# BQ51003YFPT_WirelessCharger_2_5W.net
KiCad netlist of a schematic drawn in Altium Designer
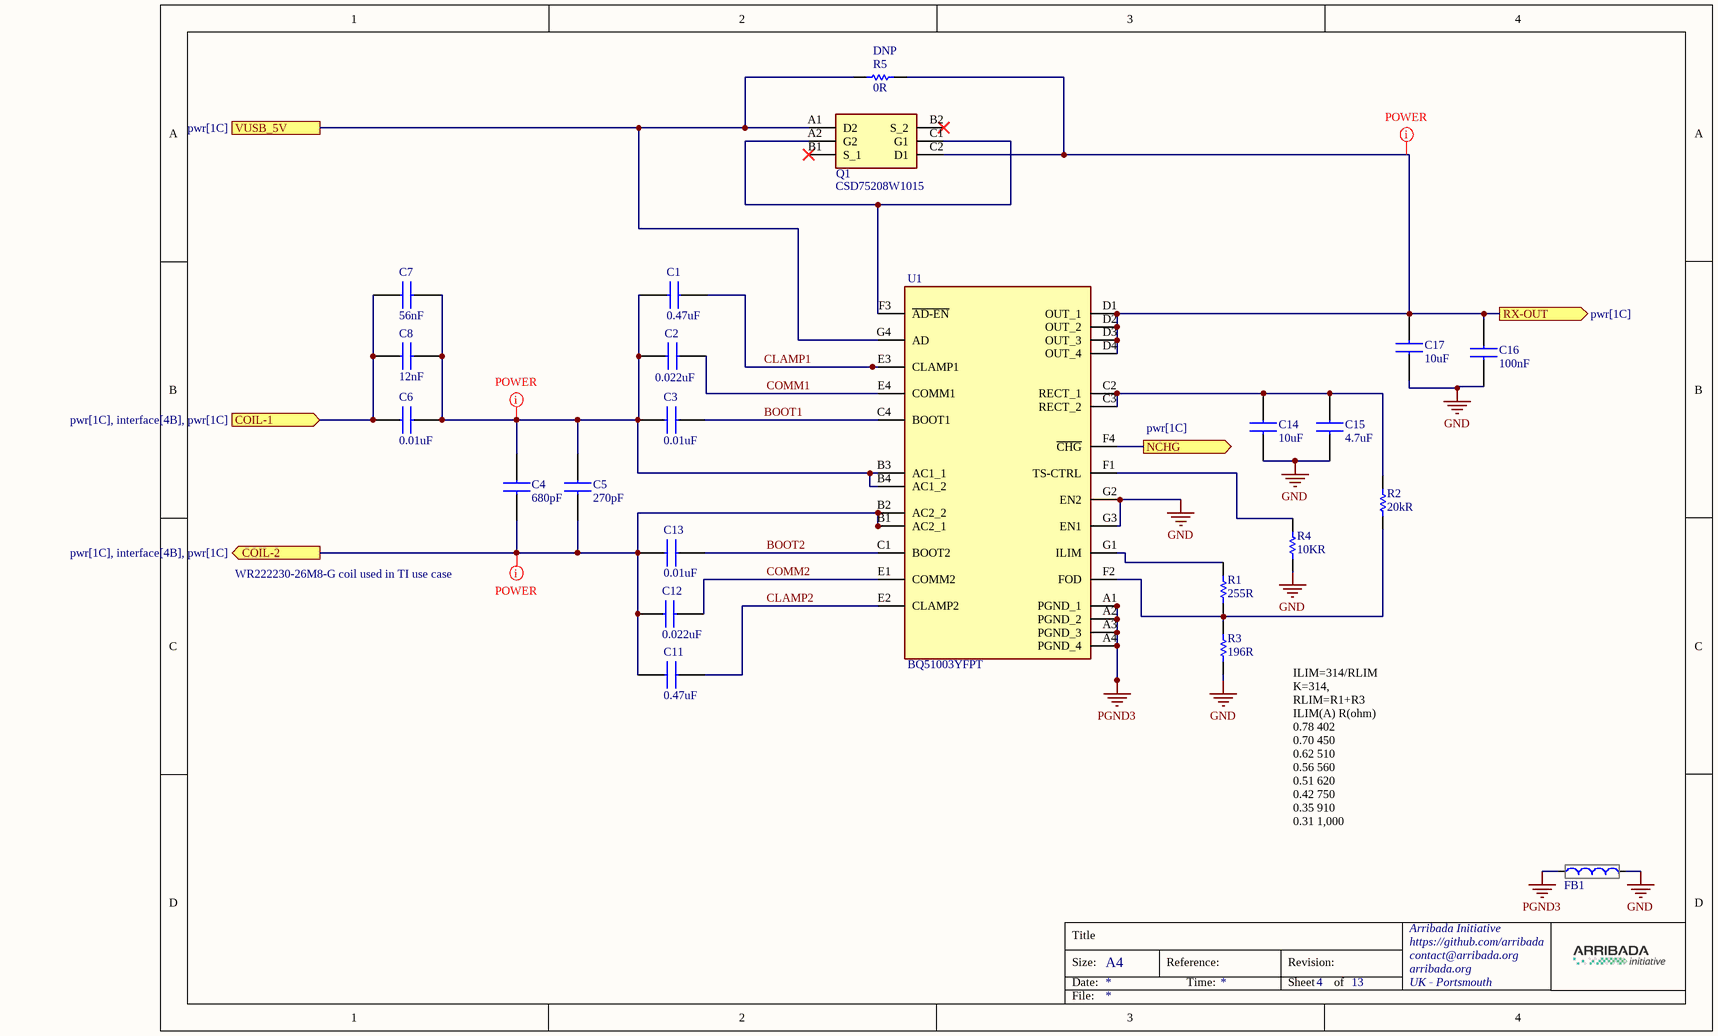
[diagram p0: BQ51003YFPT_WirelessCharger_2.5W.SchDoc]

(export (version "E")
  (design (tool "Eeschema 10.0.6"))
  (components
    (comp (ref "C1")
      (value "0.47uF")
      (footprint "stm32wl-dev:GRM18x")
      (description "Multilayer Ceramic Capacitors MLCC - SMD/SMT 0.47 uF 25 VDC 10% 0603 X7R")
      (fields
        (field (name "MANUFACTURER_PART_NUMBER") "GRM188R71E474KA12D")
        (field (name "MOUSER PART NUMBER") "81-GRM188R71E474KA12")
      )
      (libsource (lib "stm32wl-dev") (part "GRM188R71E474KA12D"))
    )
    (comp (ref "C2")
      (value "0.022uF")
      (footprint "stm32wl-dev:GRM15x")
      (description "Multilayer Ceramic Capacitors MLCC - SMD/SMT 0.022 uF 25 VDC 10% 0402 X7R")
      (fields
        (field (name "MANUFACTURER_PART_NUMBER") "GRM155R71E223KA61D")
        (field (name "MOUSER PART NUMBER") "81-GRM155R71E223KA6D")
      )
      (libsource (lib "stm32wl-dev") (part "GRM155R71E223KA61D"))
    )
    (comp (ref "C3")
      (value "0.01uF")
      (footprint "stm32wl-dev:CAPC1005X70N")
      (description "Multilayer Ceramic Capacitors MLCC - SMD/SMT 0.01 uF 25 VDC 10% 0402 X7R")
      (fields
        (field (name "MANUFACTURER_PART_NUMBER") "GRM155R71E103KA01D")
        (field (name "MOUSER PART NUMBER") "81-GRM36X103K25")
      )
      (libsource (lib "stm32wl-dev") (part "GRM155R71E103KA01D"))
    )
    (comp (ref "C4")
      (value "680pF")
      (footprint "stm32wl-dev:CAPC1005X70N")
      (description "Multilayer Ceramic Capacitors MLCC - SMD/SMT 680 pF 50 VDC 10% 0402 X7R")
      (fields
        (field (name "MANUFACTURER_PART_NUMBER") "GRM155R71H681KA01D")
        (field (name "MOUSER PART NUMBER") "81-GRM15R71H681KA01D")
      )
      (libsource (lib "stm32wl-dev") (part "GRM155R71H681KA01D"))
    )
    (comp (ref "C5")
      (value "270pF")
      (footprint "stm32wl-dev:CAPC1005X70N")
      (description "Multilayer Ceramic Capacitors MLCC - SMD/SMT 270 pF 50 VDC 10% 0402 X7R")
      (fields
        (field (name "MANUFACTURER_PART_NUMBER") "GRM155R71H271KA01J")
        (field (name "MOUSER PART NUMBER") "81-GRM155R71H271KA1J")
      )
      (libsource (lib "stm32wl-dev") (part "GRM155R71H271KA01J"))
    )
    (comp (ref "C6")
      (value "0.01uF")
      (footprint "stm32wl-dev:CAPC1608X90N")
      (description "Multilayer Ceramic Capacitors MLCC - SMD/SMT .01UF 50V 10% 0603")
      (fields
        (field (name "MANUFACTURER_PART_NUMBER") "GRM188R71H103KA01D")
        (field (name "MOUSER PART NUMBER") "81-GRM39X103K50D")
      )
      (libsource (lib "stm32wl-dev") (part "GRM188R71H103KA01D"))
    )
    (comp (ref "C7")
      (value "56nF")
      (footprint "stm32wl-dev:CAPC1608X90N")
      (description "Multilayer Ceramic Capacitors MLCC - SMD/SMT 0.056 uF 50 VDC 10% 0603 X7R AEC-Q200")
      (fields (field (name "MANUFACTURER_PART_NUMBER") "GCJ188R71H563KA12J"))
      (libsource (lib "stm32wl-dev") (part "GCJ188R71H563KA12J"))
    )
    (comp (ref "C8")
      (value "12nF")
      (footprint "CAPC1608X90N")
      (description "Multilayer Ceramic Capacitors MLCC - SMD/SMT 50V 0.012uF X7R 0603 10%")
      (fields
        (field (name "MANUFACTURER") "KEMET")
        (field (name "MANUFACTURER PART NUMBER") "C0603C123K5RACTU")
      )
      (libsource (lib "stm32wl-dev") (part "C0603C123K5RACTU"))
    )
    (comp (ref "C11")
      (value "0.47uF")
      (footprint "stm32wl-dev:GRM18x")
      (description "Multilayer Ceramic Capacitors MLCC - SMD/SMT 0.47 uF 25 VDC 10% 0603 X7R")
      (fields
        (field (name "MANUFACTURER_PART_NUMBER") "GRM188R71E474KA12D")
        (field (name "MOUSER PART NUMBER") "81-GRM188R71E474KA12")
      )
      (libsource (lib "stm32wl-dev") (part "GRM188R71E474KA12D"))
    )
    (comp (ref "C12")
      (value "0.022uF")
      (footprint "stm32wl-dev:GRM15x")
      (description "Multilayer Ceramic Capacitors MLCC - SMD/SMT 0.022 uF 25 VDC 10% 0402 X7R")
      (fields
        (field (name "MANUFACTURER_PART_NUMBER") "GRM155R71E223KA61D")
        (field (name "MOUSER PART NUMBER") "81-GRM155R71E223KA6D")
      )
      (libsource (lib "stm32wl-dev") (part "GRM155R71E223KA61D"))
    )
    (comp (ref "C13")
      (value "0.01uF")
      (footprint "stm32wl-dev:CAPC1005X70N")
      (description "Multilayer Ceramic Capacitors MLCC - SMD/SMT 0.01 uF 25 VDC 10% 0402 X7R")
      (fields
        (field (name "MANUFACTURER_PART_NUMBER") "GRM155R71E103KA01D")
        (field (name "MOUSER PART NUMBER") "81-GRM36X103K25")
      )
      (libsource (lib "stm32wl-dev") (part "GRM155R71E103KA01D"))
    )
    (comp (ref "C14")
      (value "EMK107BBJ106MA-T")
      (footprint "stm32wl-dev:CAPC1709X100N")
      (description "Multilayer Ceramic Capacitors MLCC - SMD/SMT 963-MSASE168BB5106MT RPLCMT PN 16V 10uF X5R 0603 20%")
      (fields (field (name "MOUSER PART NUMBER") "963-EMK107BBJ106MA-T") (field (name "PARAMETER 1") "10uF"))
      (libsource (lib "stm32wl-dev") (part "EMK107BBJ106MA-T"))
    )
    (comp (ref "C15")
      (value "4.7uF")
      (footprint "stm32wl-dev:CAPC1608X90N")
      (description "Multilayer Ceramic Capacitors MLCC - SMD/SMT 4.7 uF 16 VDC 10% 0603 X5R")
      (fields
        (field (name "MANUFACTURER_PART_NUMBER") "GRM188R61C475KE11J")
        (field (name "MOUSER PART NUMBER") "81-GRM188R61C475KE1J")
      )
      (libsource (lib "stm32wl-dev") (part "GRM188R61C475KE11J"))
    )
    (comp (ref "C16")
      (value "100nF")
      (footprint "0402")
      (description "Multilayer Ceramic Capacitors MLCC - SMD/SMT 0.1 uF 16 VDC 10% 0402 X7R")
      (fields
        (field (name "MANUFACTURER_PART_NUMBER") "CC0402KRX7R7BB104")
        (field (name "MANUFACTURER") "YAGEO")
      )
      (libsource (lib "stm32wl-dev") (part "GRM155R71C104KA88D"))
    )
    (comp (ref "C17")
      (value "EMK107BBJ106MA-T")
      (footprint "stm32wl-dev:CAPC1709X100N")
      (description "Multilayer Ceramic Capacitors MLCC - SMD/SMT 963-MSASE168BB5106MT RPLCMT PN 16V 10uF X5R 0603 20%")
      (fields (field (name "MOUSER PART NUMBER") "963-EMK107BBJ106MA-T") (field (name "PARAMETER 1") "10uF"))
      (libsource (lib "stm32wl-dev") (part "EMK107BBJ106MA-T"))
    )
    (comp (ref "FB1")
      (value "BLM18AG102SN1D")
      (footprint "stm32wl-dev:BLM18SP221SN1B")
      (description "Ferrite Bead - 1000 OHM 25%")
      (fields (field (name "MOUSER PART NUMBER") "81-BLM11A102S"))
      (libsource (lib "stm32wl-dev") (part "BLM18AG102SN1D"))
    )
    (comp (ref "Q1")
      (value "CSD75208W1015")
      (footprint "stm32wl-dev:BGA6C50P2X3_95X145X62")
      (description "MOSFETs 20V P-channel NexFET Pwr MOSFET A 595-CSD75208W1015T")
      (fields (field (name "MOUSER PART NUMBER") "595-CSD75208W1015"))
      (libsource (lib "stm32wl-dev") (part "CSD75208W1015"))
    )
    (comp (ref "R1")
      (value "255R")
      (footprint "stm32wl-dev:RESC0603X28N")
      (description "Thick Film Resistors - SMD 0201 255ohm 1% HalogenFree AEC-Q200")
      (fields (field (name "MANUFACTURER_PART_NUMBER") "ERJ-1GNF2550C"))
      (libsource (lib "stm32wl-dev") (part "ERJ-1GNF2550C"))
    )
    (comp (ref "R2")
      (value "20kR")
      (footprint "stm32wl-dev:RESC0603X28N")
      (description "Res Thick Film 0201 453 Ohm 1% 1/20W ±100ppm/°C Molded SMD SMD Paper T/R")
      (fields
        (field (name "MANUFACTURER_PART_NUMBER") "CRCW020120K0FKED")
        (field (name "MOUSER PART NUMBER") "71-CRCW020120K0FKED")
      )
      (libsource (lib "stm32wl-dev") (part "CRCW020120K0FKED"))
    )
    (comp (ref "R3")
      (value "196R")
      (footprint "RESC0603X28N")
      (description "Thick Film Resistors - SMD 1/20watt 196ohms 1% 100ppm")
      (fields (field (name "Comment") "CRCW0201196RFKED"))
      (libsource (lib "stm32wl-dev") (part "CRCW0201196RFKED"))
    )
    (comp (ref "R4")
      (value "10KR")
      (footprint "RESC0603X26N")
      (description "Thick Film Resistors - SMD 10 kOhms 50 mW 0201 1%")
      (fields
        (field (name "MANUFACTURER_PART_NUMBER") "RC0201FR-7D10KL")
        (field (name "MOUSER PART NUMBER") "603-RC0201FR-7D10KL")
      )
      (libsource (lib "stm32wl-dev") (part "RC0201FR-7D10KL"))
    )
    (comp (ref "R5")
      (value "DNP")
      (footprint "stm32wl-dev:RESC1005X40N")
      (description "Thick Film Resistors - SMD CRCW 402 jumper")
      (fields
        (field (name "MANUFACTURER_PART_NUMBER") "CRCW04020000Z0EEHP")
        (field (name "MOUSER PART NUMBER") "71-CRCW04020000Z0EEH")
        (field (name "ALTIUM_VALUE") "0R")
      )
      (libsource (lib "stm32wl-dev") (part "CRCW04020000Z0EEHP"))
    )
    (comp (ref "U1")
      (value "BQ51003YFPT")
      (footprint "stm32wl-dev:BGA28C40P4X7_188X301X50")
      (description "Wireless Charging ICs Wireless Pwr Receivr A 595-BQ51003YFPR")
      (fields (field (name "MOUSER PART NUMBER") "595-BQ51003YFPT"))
      (libsource (lib "stm32wl-dev") (part "BQ51003YFPT"))
    )
  )
  (nets
    (net (code "1") (name "/BOOT1") (class "Default")
      (node (ref "C3") (pin "2") (pinfunction "2_2") (pintype "passive"))
      (node (ref "U1") (pin "C4") (pinfunction "BOOT1_C4") (pintype "passive"))
    )
    (net (code "2") (name "/BOOT2") (class "Default")
      (node (ref "C13") (pin "2") (pinfunction "2_2") (pintype "passive"))
      (node (ref "U1") (pin "C1") (pinfunction "BOOT2_C1") (pintype "passive"))
    )
    (net (code "3") (name "/CLAMP1") (class "Default")
      (node (ref "C1") (pin "2") (pinfunction "2_2") (pintype "passive"))
      (node (ref "U1") (pin "E3") (pinfunction "CLAMP1_E3") (pintype "passive"))
    )
    (net (code "4") (name "/CLAMP2") (class "Default")
      (node (ref "C11") (pin "2") (pinfunction "2_2") (pintype "passive"))
      (node (ref "U1") (pin "E2") (pinfunction "CLAMP2_E2") (pintype "passive"))
    )
    (net (code "5") (name "/COIL-1") (class "Default")
      (node (ref "C6") (pin "1") (pinfunction "1_1") (pintype "passive"))
      (node (ref "C7") (pin "1") (pinfunction "1_1") (pintype "passive"))
      (node (ref "C8") (pin "1") (pinfunction "1_1") (pintype "passive"))
    )
    (net (code "6") (name "/COIL-2") (class "Default")
      (node (ref "C11") (pin "1") (pinfunction "1_1") (pintype "passive"))
      (node (ref "C12") (pin "1") (pinfunction "1_1") (pintype "passive"))
      (node (ref "C13") (pin "1") (pinfunction "1_1") (pintype "passive"))
      (node (ref "C4") (pin "1") (pinfunction "1_1") (pintype "passive"))
      (node (ref "C5") (pin "1") (pinfunction "1_1") (pintype "passive"))
      (node (ref "U1") (pin "B1") (pinfunction "AC2_1_B1") (pintype "passive"))
      (node (ref "U1") (pin "B2") (pinfunction "AC2_2_B2") (pintype "passive"))
    )
    (net (code "7") (name "/COMM1") (class "Default")
      (node (ref "C2") (pin "2") (pinfunction "2_2") (pintype "passive"))
      (node (ref "U1") (pin "E4") (pinfunction "COMM1_E4") (pintype "passive"))
    )
    (net (code "8") (name "/COMM2") (class "Default")
      (node (ref "C12") (pin "2") (pinfunction "2_2") (pintype "passive"))
      (node (ref "U1") (pin "E1") (pinfunction "COMM2_E1") (pintype "passive"))
    )
    (net (code "9") (name "/NCHG") (class "Default")
      (node (ref "U1") (pin "F4") (pinfunction "~{CHG}_F4") (pintype "passive"))
    )
    (net (code "10") (name "/RX-OUT") (class "Default")
      (node (ref "C16") (pin "1") (pinfunction "1_1") (pintype "passive"))
      (node (ref "C17") (pin "1") (pinfunction "1_1") (pintype "passive"))
      (node (ref "Q1") (pin "C2") (pinfunction "D1_C2") (pintype "passive"))
      (node (ref "R5") (pin "2") (pinfunction "2_2") (pintype "passive"))
      (node (ref "U1") (pin "D1") (pinfunction "OUT_1_D1") (pintype "passive"))
      (node (ref "U1") (pin "D2") (pinfunction "OUT_2_D2") (pintype "passive"))
      (node (ref "U1") (pin "D3") (pinfunction "OUT_3_D3") (pintype "passive"))
      (node (ref "U1") (pin "D4") (pinfunction "OUT_4_D4") (pintype "passive"))
    )
    (net (code "11") (name "/VUSB_5V") (class "Default")
      (node (ref "Q1") (pin "A1") (pinfunction "D2_A1") (pintype "passive"))
      (node (ref "R5") (pin "1") (pinfunction "1_1") (pintype "passive"))
      (node (ref "U1") (pin "G4") (pinfunction "AD_G4") (pintype "passive"))
    )
    (net (code "12") (name "GND") (class "Default")
      (node (ref "C14") (pin "2") (pinfunction "2_2") (pintype "passive"))
      (node (ref "C15") (pin "2") (pinfunction "2_2") (pintype "passive"))
      (node (ref "C16") (pin "2") (pinfunction "2_2") (pintype "passive"))
      (node (ref "C17") (pin "2") (pinfunction "2_2") (pintype "passive"))
      (node (ref "FB1") (pin "2") (pinfunction "2_2") (pintype "passive"))
      (node (ref "R3") (pin "2") (pinfunction "2_2") (pintype "passive"))
      (node (ref "R4") (pin "2") (pinfunction "2_2") (pintype "passive"))
      (node (ref "U1") (pin "G2") (pinfunction "EN2_G2") (pintype "passive"))
      (node (ref "U1") (pin "G3") (pinfunction "EN1_G3") (pintype "passive"))
    )
    (net (code "13") (name "Net-(Q1-G1)") (class "Default")
      (node (ref "Q1") (pin "A2") (pinfunction "G2_A2") (pintype "passive"))
      (node (ref "Q1") (pin "C1") (pinfunction "G1_C1") (pintype "passive"))
      (node (ref "U1") (pin "F3") (pinfunction "~{AD-EN}_F3") (pintype "passive"))
    )
    (net (code "14") (name "Net-(U1-AC1_1)") (class "Default")
      (node (ref "C1") (pin "1") (pinfunction "1_1") (pintype "passive"))
      (node (ref "C2") (pin "1") (pinfunction "1_1") (pintype "passive"))
      (node (ref "C3") (pin "1") (pinfunction "1_1") (pintype "passive"))
      (node (ref "C4") (pin "2") (pinfunction "2_2") (pintype "passive"))
      (node (ref "C5") (pin "2") (pinfunction "2_2") (pintype "passive"))
      (node (ref "C6") (pin "2") (pinfunction "2_2") (pintype "passive"))
      (node (ref "C7") (pin "2") (pinfunction "2_2") (pintype "passive"))
      (node (ref "C8") (pin "2") (pinfunction "2_2") (pintype "passive"))
      (node (ref "U1") (pin "B3") (pinfunction "AC1_1_B3") (pintype "passive"))
      (node (ref "U1") (pin "B4") (pinfunction "AC1_2_B4") (pintype "passive"))
    )
    (net (code "15") (name "Net-(U1-FOD)") (class "Default")
      (node (ref "R1") (pin "1") (pinfunction "1_1") (pintype "passive"))
      (node (ref "R2") (pin "2") (pinfunction "2_2") (pintype "passive"))
      (node (ref "R3") (pin "1") (pinfunction "1_1") (pintype "passive"))
      (node (ref "U1") (pin "F2") (pinfunction "FOD_F2") (pintype "passive"))
    )
    (net (code "16") (name "Net-(U1-ILIM)") (class "Default")
      (node (ref "R1") (pin "2") (pinfunction "2_2") (pintype "passive"))
      (node (ref "U1") (pin "G1") (pinfunction "ILIM_G1") (pintype "passive"))
    )
    (net (code "17") (name "Net-(U1-RECT_1)") (class "Default")
      (node (ref "C14") (pin "1") (pinfunction "1_1") (pintype "passive"))
      (node (ref "C15") (pin "1") (pinfunction "1_1") (pintype "passive"))
      (node (ref "R2") (pin "1") (pinfunction "1_1") (pintype "passive"))
      (node (ref "U1") (pin "C2") (pinfunction "RECT_1_C2") (pintype "passive"))
      (node (ref "U1") (pin "C3") (pinfunction "RECT_2_C3") (pintype "passive"))
    )
    (net (code "18") (name "Net-(U1-TS-CTRL)") (class "Default")
      (node (ref "R4") (pin "1") (pinfunction "1_1") (pintype "passive"))
      (node (ref "U1") (pin "F1") (pinfunction "TS-CTRL_F1") (pintype "passive"))
    )
    (net (code "19") (name "PGND3") (class "Default")
      (node (ref "FB1") (pin "1") (pinfunction "1_1") (pintype "passive"))
      (node (ref "U1") (pin "A1") (pinfunction "PGND_1_A1") (pintype "passive"))
      (node (ref "U1") (pin "A2") (pinfunction "PGND_2_A2") (pintype "passive"))
      (node (ref "U1") (pin "A3") (pinfunction "PGND_3_A3") (pintype "passive"))
      (node (ref "U1") (pin "A4") (pinfunction "PGND_4_A4") (pintype "passive"))
    )
    (net (code "20") (name "unconnected-(Q1-S_1-PadB1)") (class "Default")
      (node (ref "Q1") (pin "B1") (pinfunction "S_1_B1") (pintype "passive+no_connect"))
    )
    (net (code "21") (name "unconnected-(Q1-S_2-PadB2)") (class "Default")
      (node (ref "Q1") (pin "B2") (pinfunction "S_2_B2") (pintype "passive+no_connect"))
    )
  )
)
